# ETH_Wifi.net
KiCad netlist of a schematic drawn in Altium Designer
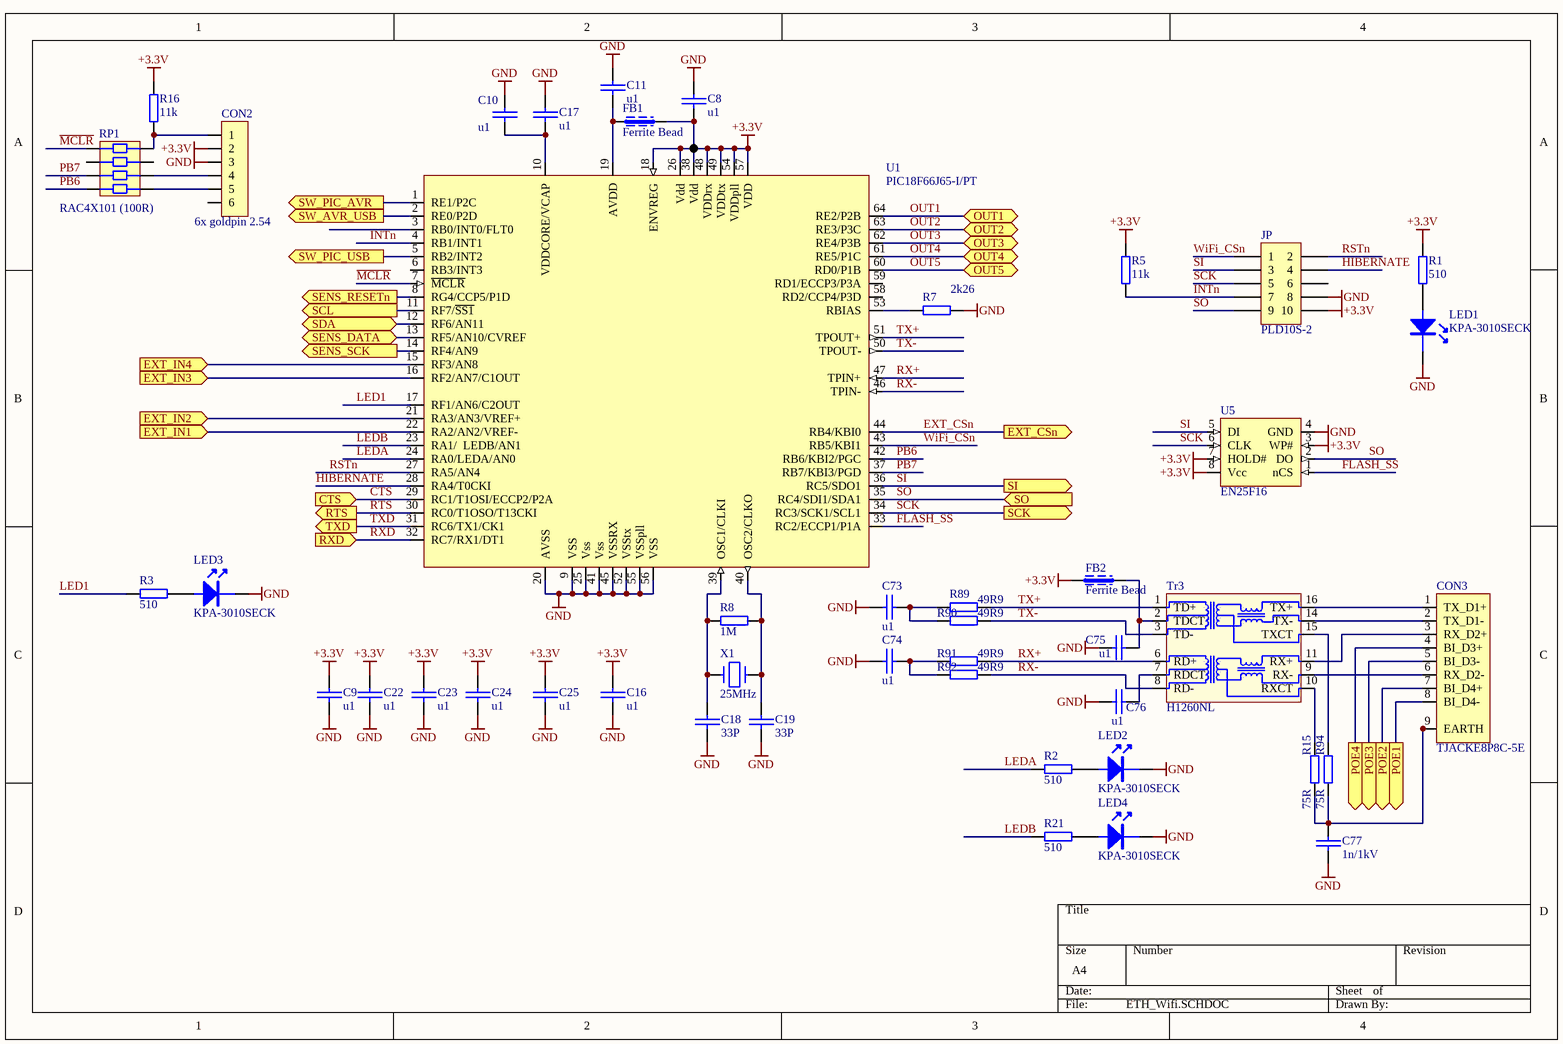
[diagram p0: ETH_Wifi.SCHDOC]

(export (version "E")
  (design (tool "Eeschema 10.0.6"))
  (components
    (comp (ref "C8")
      (value "u1")
      (footprint "0603")
      (description "Capacitor SMD")
      (libsource (lib "LIBRARY_SCH") (part "CAP_SMD"))
    )
    (comp (ref "C9")
      (value "u1")
      (footprint "0603")
      (description "Capacitor SMD")
      (libsource (lib "LIBRARY_SCH") (part "CAP_SMD"))
    )
    (comp (ref "C10")
      (value "u1")
      (footprint "0603")
      (description "Capacitor SMD")
      (libsource (lib "LIBRARY_SCH") (part "CAP_SMD"))
    )
    (comp (ref "C11")
      (value "u1")
      (footprint "0603")
      (description "Capacitor SMD")
      (libsource (lib "LIBRARY_SCH") (part "CAP_SMD"))
    )
    (comp (ref "C16")
      (value "u1")
      (footprint "0603")
      (description "Capacitor SMD")
      (libsource (lib "LIBRARY_SCH") (part "CAP_SMD"))
    )
    (comp (ref "C17")
      (value "u1")
      (footprint "0603")
      (description "Capacitor SMD")
      (libsource (lib "LIBRARY_SCH") (part "CAP_SMD"))
    )
    (comp (ref "C18")
      (value "33P")
      (footprint "0603")
      (description "Capacitor SMD")
      (libsource (lib "LIBRARY_SCH") (part "CAP_SMD"))
    )
    (comp (ref "C19")
      (value "33P")
      (footprint "0603")
      (description "Capacitor SMD")
      (libsource (lib "LIBRARY_SCH") (part "CAP_SMD"))
    )
    (comp (ref "C22")
      (value "u1")
      (footprint "0603")
      (description "Capacitor SMD")
      (libsource (lib "LIBRARY_SCH") (part "CAP_SMD"))
    )
    (comp (ref "C23")
      (value "u1")
      (footprint "0603")
      (description "Capacitor SMD")
      (libsource (lib "LIBRARY_SCH") (part "CAP_SMD"))
    )
    (comp (ref "C24")
      (value "u1")
      (footprint "0603")
      (description "Capacitor SMD")
      (libsource (lib "LIBRARY_SCH") (part "CAP_SMD"))
    )
    (comp (ref "C25")
      (value "u1")
      (footprint "0603")
      (description "Capacitor SMD")
      (libsource (lib "LIBRARY_SCH") (part "CAP_SMD"))
    )
    (comp (ref "C73")
      (value "u1")
      (footprint "0603")
      (description "Capacitor SMD")
      (libsource (lib "*") (part "CAP_SMD"))
    )
    (comp (ref "C74")
      (value "u1")
      (footprint "0603")
      (description "Capacitor SMD")
      (libsource (lib "*") (part "CAP_SMD"))
    )
    (comp (ref "C75")
      (value "u1")
      (footprint "0603")
      (description "Capacitor SMD")
      (libsource (lib "LIBRARY_SCH") (part "CAP_SMD"))
    )
    (comp (ref "C76")
      (value "u1")
      (footprint "0603")
      (description "Capacitor SMD")
      (libsource (lib "LIBRARY_SCH") (part "CAP_SMD"))
    )
    (comp (ref "C77")
      (value "1n/1kV")
      (footprint "cap_ceram")
      (description "Capacitor")
      (libsource (lib "LIBRARY_SCH") (part "CAP"))
    )
    (comp (ref "CON2") (value "6x goldpin 2.54") (footprint "SIP6") (libsource (lib "*") (part "CON6")))
    (comp (ref "CON3")
      (value "TJACKE8P8C-5E")
      (footprint "TJACKE8P8C-5E")
      (description "RJ 45 connector (Maritex)")
      (libsource (lib "LIBRARY_SCH") (part "CON_RJ45_shielded"))
    )
    (comp (ref "FB1")
      (value "Ferrite Bead")
      (footprint "0603")
      (description "ferrite bead")
      (libsource (lib "*") (part "L_FERRITE_BEAD"))
    )
    (comp (ref "FB2")
      (value "Ferrite Bead")
      (footprint "0603")
      (description "ferrite bead")
      (libsource (lib "*") (part "L_FERRITE_BEAD"))
    )
    (comp (ref "JP")
      (value "PLD10S-2")
      (footprint "HEADER5X2")
      (description "Goldpin 2.54mm")
      (libsource (lib "LIBRARY_SCH") (part "CON_HEADER 5X2"))
    )
    (comp (ref "LED1")
      (value "KPA-3010SECK")
      (footprint "LED_KPA3010")
      (description "LED (TME)")
      (libsource (lib "LIBRARY_SCH") (part "LED_SMD_90deg"))
    )
    (comp (ref "LED2")
      (value "KPA-3010SECK")
      (footprint "LED_KPA3010")
      (description "LED (TME)")
      (libsource (lib "LIBRARY_SCH") (part "LED_SMD_90deg"))
    )
    (comp (ref "LED3")
      (value "KPA-3010SECK")
      (footprint "LED_KPA3010")
      (description "LED (TME)")
      (libsource (lib "LIBRARY_SCH") (part "LED_SMD_90deg"))
    )
    (comp (ref "LED4")
      (value "KPA-3010SECK")
      (footprint "LED_KPA3010")
      (description "LED (TME)")
      (libsource (lib "LIBRARY_SCH") (part "LED_SMD_90deg"))
    )
    (comp (ref "R1")
      (value "510")
      (footprint "0603")
      (description "SMD Resistor")
      (libsource (lib "LIBRARY_SCH") (part "RES_SMD"))
    )
    (comp (ref "R2")
      (value "510")
      (footprint "0603")
      (description "SMD Resistor")
      (libsource (lib "LIBRARY_SCH") (part "RES_SMD"))
    )
    (comp (ref "R3")
      (value "510")
      (footprint "0603")
      (description "SMD Resistor")
      (libsource (lib "LIBRARY_SCH") (part "RES_SMD"))
    )
    (comp (ref "R5")
      (value "11k")
      (footprint "0603")
      (description "SMD Resistor")
      (libsource (lib "*") (part "RES_SMD"))
    )
    (comp (ref "R7")
      (value "2k26")
      (footprint "0603")
      (description "SMD Resistor")
      (libsource (lib "LIBRARY_SCH") (part "RES_SMD"))
    )
    (comp (ref "R8")
      (value "1M")
      (footprint "0603")
      (description "SMD Resistor")
      (libsource (lib "*") (part "RES_SMD"))
    )
    (comp (ref "R15")
      (value "75R")
      (footprint "0603")
      (description "SMD Resistor")
      (libsource (lib "*") (part "RES_SMD"))
    )
    (comp (ref "R16")
      (value "11k")
      (footprint "0603")
      (description "SMD Resistor")
      (libsource (lib "*") (part "RES_SMD"))
    )
    (comp (ref "R21")
      (value "510")
      (footprint "0603")
      (description "SMD Resistor")
      (libsource (lib "LIBRARY_SCH") (part "RES_SMD"))
    )
    (comp (ref "R89")
      (value "49R9")
      (footprint "0603")
      (description "SMD Resistor")
      (libsource (lib "LIBRARY_SCH") (part "RES_SMD"))
    )
    (comp (ref "R90")
      (value "49R9")
      (footprint "0603")
      (description "SMD Resistor")
      (libsource (lib "*") (part "RES_SMD"))
    )
    (comp (ref "R91")
      (value "49R9")
      (footprint "0603")
      (description "SMD Resistor")
      (libsource (lib "*") (part "RES_SMD"))
    )
    (comp (ref "R92")
      (value "49R9")
      (footprint "0603")
      (description "SMD Resistor")
      (libsource (lib "*") (part "RES_SMD"))
    )
    (comp (ref "R94")
      (value "75R")
      (footprint "0603")
      (description "SMD Resistor")
      (libsource (lib "*") (part "RES_SMD"))
    )
    (comp (ref "RP1")
      (value "RAC4X101 (100R)")
      (footprint "CAY-16")
      (description "Resistor network 1206 (4x0402) Maritex RAC4Xxxx")
      (libsource (lib "LIBRARY_SCH") (part "CAY-16"))
    )
    (comp (ref "Tr3")
      (value "H1260NL")
      (footprint "H1260NL")
      (description "ethernet trafo (TME)")
      (libsource (lib "*") (part "TR_H1260NL"))
    )
    (comp (ref "U1")
      (value "PIC18F66J65-I/PT")
      (footprint "TQFP64-MAX")
      (libsource (lib "LIBRARY_SCH") (part "PIC18F66J60"))
    )
    (comp (ref "U5")
      (value "EN25F16")
      (footprint "SO-8L")
      (description "FLASH (maritex)")
      (libsource (lib "LIBRARY_SCH") (part "MEM_EN25F16"))
    )
    (comp (ref "X1")
      (value "25MHz")
      (footprint "HC-49SM")
      (description "Crystal oscillator")
      (libsource (lib "LIBRARY_SCH") (part "CRYSTAL"))
    )
  )
  (nets
    (net (code "1") (name "+3.3V") (class "Default")
      (node (ref "C16") (pin "1") (pinfunction "1_1") (pintype "passive"))
      (node (ref "C22") (pin "1") (pinfunction "1_1") (pintype "passive"))
      (node (ref "C23") (pin "1") (pinfunction "1_1") (pintype "passive"))
      (node (ref "C24") (pin "1") (pinfunction "1_1") (pintype "passive"))
      (node (ref "C25") (pin "1") (pinfunction "1_1") (pintype "passive"))
      (node (ref "C8") (pin "2") (pinfunction "2_2") (pintype "passive"))
      (node (ref "C9") (pin "2") (pinfunction "2_2") (pintype "passive"))
      (node (ref "CON2") (pin "2") (pinfunction "2_2") (pintype "passive"))
      (node (ref "FB1") (pin "2") (pinfunction "2_2") (pintype "passive"))
      (node (ref "FB2") (pin "1") (pinfunction "1_1") (pintype "passive"))
      (node (ref "JP") (pin "10") (pinfunction "10_10") (pintype "passive"))
      (node (ref "R1") (pin "1") (pinfunction "1_1") (pintype "passive"))
      (node (ref "R16") (pin "2") (pinfunction "2_2") (pintype "passive"))
      (node (ref "R5") (pin "2") (pinfunction "2_2") (pintype "passive"))
      (node (ref "U1") (pin "18") (pinfunction "ENVREG_18") (pintype "input"))
      (node (ref "U1") (pin "26") (pinfunction "Vdd_26") (pintype "power_in"))
      (node (ref "U1") (pin "38") (pinfunction "Vdd_38") (pintype "power_in"))
      (node (ref "U1") (pin "48") (pinfunction "VDDrx_48") (pintype "power_in"))
      (node (ref "U1") (pin "49") (pinfunction "VDDtx_49") (pintype "power_in"))
      (node (ref "U1") (pin "54") (pinfunction "VDDpll_54") (pintype "power_in"))
      (node (ref "U1") (pin "57") (pinfunction "VDD_57") (pintype "power_in"))
      (node (ref "U5") (pin "3") (pinfunction "WP#_3") (pintype "input"))
      (node (ref "U5") (pin "7") (pinfunction "HOLD#_7") (pintype "input"))
      (node (ref "U5") (pin "8") (pinfunction "Vcc_8") (pintype "passive"))
    )
    (net (code "2") (name "/CTS") (class "Default")
      (node (ref "U1") (pin "29") (pinfunction "RC1/T1OSI/ECCP2/P2A_29") (pintype "bidirectional"))
    )
    (net (code "3") (name "/EXT_CSn") (class "Default")
      (node (ref "U1") (pin "44") (pinfunction "RB4/KBI0_44") (pintype "bidirectional"))
    )
    (net (code "4") (name "/EXT_IN1") (class "Default")
      (node (ref "U1") (pin "22") (pinfunction "RA2/AN2/VREF-_22") (pintype "bidirectional"))
    )
    (net (code "5") (name "/EXT_IN2") (class "Default")
      (node (ref "U1") (pin "21") (pinfunction "RA3/AN3/VREF+_21") (pintype "bidirectional"))
    )
    (net (code "6") (name "/EXT_IN3") (class "Default")
      (node (ref "U1") (pin "16") (pinfunction "RF2/AN7/C1OUT_16") (pintype "bidirectional"))
    )
    (net (code "7") (name "/EXT_IN4") (class "Default")
      (node (ref "U1") (pin "15") (pinfunction "RF3/AN8_15") (pintype "bidirectional"))
    )
    (net (code "8") (name "/FLASH_SS") (class "Default")
      (node (ref "U1") (pin "33") (pinfunction "RC2/ECCP1/P1A_33") (pintype "bidirectional"))
      (node (ref "U5") (pin "1") (pinfunction "nCS_1") (pintype "input"))
    )
    (net (code "9") (name "/HIBERNATE") (class "Default")
      (node (ref "JP") (pin "4") (pinfunction "4_4") (pintype "passive"))
      (node (ref "U1") (pin "28") (pinfunction "RA4/T0CKI_28") (pintype "bidirectional"))
    )
    (net (code "10") (name "/INTn") (class "Default")
      (node (ref "JP") (pin "7") (pinfunction "7_7") (pintype "passive"))
      (node (ref "R5") (pin "1") (pinfunction "1_1") (pintype "passive"))
      (node (ref "U1") (pin "4") (pinfunction "RB1/INT1_4") (pintype "bidirectional"))
    )
    (net (code "11") (name "/LED1") (class "Default")
      (node (ref "R3") (pin "2") (pinfunction "2_2") (pintype "passive"))
      (node (ref "U1") (pin "17") (pinfunction "RF1/AN6/C2OUT_17") (pintype "bidirectional"))
    )
    (net (code "12") (name "/LEDA") (class "Default")
      (node (ref "R2") (pin "2") (pinfunction "2_2") (pintype "passive"))
      (node (ref "U1") (pin "24") (pinfunction "RA0/LEDA/AN0_24") (pintype "bidirectional"))
    )
    (net (code "13") (name "/LEDB") (class "Default")
      (node (ref "R21") (pin "2") (pinfunction "2_2") (pintype "passive"))
      (node (ref "U1") (pin "23") (pinfunction "RA1/__LEDB/AN1_23") (pintype "bidirectional"))
    )
    (net (code "14") (name "/OUT1") (class "Default")
      (node (ref "U1") (pin "64") (pinfunction "RE2/P2B_64") (pintype "bidirectional"))
    )
    (net (code "15") (name "/OUT2") (class "Default")
      (node (ref "U1") (pin "63") (pinfunction "RE3/P3C_63") (pintype "bidirectional"))
    )
    (net (code "16") (name "/OUT3") (class "Default")
      (node (ref "U1") (pin "62") (pinfunction "RE4/P3B_62") (pintype "bidirectional"))
    )
    (net (code "17") (name "/OUT4") (class "Default")
      (node (ref "U1") (pin "61") (pinfunction "RE5/P1C_61") (pintype "bidirectional"))
    )
    (net (code "18") (name "/OUT5") (class "Default")
      (node (ref "U1") (pin "60") (pinfunction "RD0/P1B_60") (pintype "bidirectional"))
    )
    (net (code "19") (name "/PB6") (class "Default")
      (node (ref "RP1") (pin "4") (pinfunction "4_4") (pintype "passive"))
      (node (ref "U1") (pin "42") (pinfunction "RB6/KBI2/PGC_42") (pintype "bidirectional"))
    )
    (net (code "20") (name "/PB7") (class "Default")
      (node (ref "RP1") (pin "3") (pinfunction "3_3") (pintype "passive"))
      (node (ref "U1") (pin "37") (pinfunction "RB7/KBI3/PGD_37") (pintype "bidirectional"))
    )
    (net (code "21") (name "/POE1") (class "Default")
      (node (ref "CON3") (pin "8") (pinfunction "BI_D4-_8") (pintype "passive"))
    )
    (net (code "22") (name "/POE2") (class "Default")
      (node (ref "CON3") (pin "7") (pinfunction "BI_D4+_7") (pintype "passive"))
    )
    (net (code "23") (name "/POE3") (class "Default")
      (node (ref "CON3") (pin "5") (pinfunction "BI_D3-_5") (pintype "passive"))
    )
    (net (code "24") (name "/POE4") (class "Default")
      (node (ref "CON3") (pin "4") (pinfunction "BI_D3+_4") (pintype "passive"))
    )
    (net (code "25") (name "/RSTn") (class "Default")
      (node (ref "JP") (pin "2") (pinfunction "2_2") (pintype "passive"))
      (node (ref "U1") (pin "27") (pinfunction "RA5/AN4_27") (pintype "bidirectional"))
    )
    (net (code "26") (name "/RTS") (class "Default")
      (node (ref "U1") (pin "30") (pinfunction "RC0/T1OSO/T13CKI_30") (pintype "bidirectional"))
    )
    (net (code "27") (name "/RX+") (class "Default")
      (node (ref "R91") (pin "2") (pinfunction "2_2") (pintype "passive"))
      (node (ref "Tr3") (pin "6") (pinfunction "RD+_6") (pintype "passive"))
      (node (ref "U1") (pin "47") (pinfunction "TPIN+_47") (pintype "input"))
    )
    (net (code "28") (name "/RX-") (class "Default")
      (node (ref "R92") (pin "2") (pinfunction "2_2") (pintype "passive"))
      (node (ref "Tr3") (pin "8") (pinfunction "RD-_8") (pintype "passive"))
      (node (ref "U1") (pin "46") (pinfunction "TPIN-_46") (pintype "input"))
    )
    (net (code "29") (name "/RXD") (class "Default")
      (node (ref "U1") (pin "32") (pinfunction "RC7/RX1/DT1_32") (pintype "bidirectional"))
    )
    (net (code "30") (name "/SCK") (class "Default")
      (node (ref "JP") (pin "5") (pinfunction "5_5") (pintype "passive"))
      (node (ref "U1") (pin "34") (pinfunction "RC3/SCK1/SCL1_34") (pintype "bidirectional"))
      (node (ref "U5") (pin "6") (pinfunction "CLK_6") (pintype "input"))
    )
    (net (code "31") (name "/SCL") (class "Default")
      (node (ref "U1") (pin "11") (pinfunction "RF7/~{SS1}_11") (pintype "bidirectional"))
    )
    (net (code "32") (name "/SDA") (class "Default")
      (node (ref "U1") (pin "12") (pinfunction "RF6/AN11_12") (pintype "bidirectional"))
    )
    (net (code "33") (name "/SENS_DATA") (class "Default")
      (node (ref "U1") (pin "13") (pinfunction "RF5/AN10/CVREF_13") (pintype "bidirectional"))
    )
    (net (code "34") (name "/SENS_RESETn") (class "Default")
      (node (ref "U1") (pin "8") (pinfunction "RG4/CCP5/P1D_8") (pintype "bidirectional"))
    )
    (net (code "35") (name "/SENS_SCK") (class "Default")
      (node (ref "U1") (pin "14") (pinfunction "RF4/AN9_14") (pintype "bidirectional"))
    )
    (net (code "36") (name "/SI") (class "Default")
      (node (ref "JP") (pin "3") (pinfunction "3_3") (pintype "passive"))
      (node (ref "U1") (pin "36") (pinfunction "RC5/SDO1_36") (pintype "bidirectional"))
      (node (ref "U5") (pin "5") (pinfunction "DI_5") (pintype "input"))
    )
    (net (code "37") (name "/SO") (class "Default")
      (node (ref "JP") (pin "9") (pinfunction "9_9") (pintype "passive"))
      (node (ref "U1") (pin "35") (pinfunction "RC4/SDI1/SDA1_35") (pintype "bidirectional"))
      (node (ref "U5") (pin "2") (pinfunction "DO_2") (pintype "output"))
    )
    (net (code "38") (name "/SW_AVR_USB") (class "Default")
      (node (ref "U1") (pin "2") (pinfunction "RE0/P2D_2") (pintype "bidirectional"))
    )
    (net (code "39") (name "/SW_PIC_AVR") (class "Default")
      (node (ref "U1") (pin "1") (pinfunction "RE1/P2C_1") (pintype "bidirectional"))
    )
    (net (code "40") (name "/SW_PIC_USB") (class "Default")
      (node (ref "U1") (pin "5") (pinfunction "RB2/INT2_5") (pintype "bidirectional"))
    )
    (net (code "41") (name "/TX+") (class "Default")
      (node (ref "R89") (pin "2") (pinfunction "2_2") (pintype "passive"))
      (node (ref "Tr3") (pin "1") (pinfunction "TD+_1") (pintype "passive"))
      (node (ref "U1") (pin "51") (pinfunction "TPOUT+_51") (pintype "output"))
    )
    (net (code "42") (name "/TX-") (class "Default")
      (node (ref "R90") (pin "2") (pinfunction "2_2") (pintype "passive"))
      (node (ref "Tr3") (pin "3") (pinfunction "TD-_3") (pintype "passive"))
      (node (ref "U1") (pin "50") (pinfunction "TPOUT-_50") (pintype "output"))
    )
    (net (code "43") (name "/TXD") (class "Default")
      (node (ref "U1") (pin "31") (pinfunction "RC6/TX1/CK1_31") (pintype "bidirectional"))
    )
    (net (code "44") (name "/WiFi_CSn") (class "Default")
      (node (ref "JP") (pin "1") (pinfunction "1_1") (pintype "passive"))
      (node (ref "U1") (pin "43") (pinfunction "RB5/KBI1_43") (pintype "bidirectional"))
    )
    (net (code "45") (name "/~{MCLR}") (class "Default")
      (node (ref "RP1") (pin "1") (pinfunction "1_1") (pintype "passive"))
      (node (ref "U1") (pin "7") (pinfunction "~{MCLR}_7") (pintype "input"))
    )
    (net (code "46") (name "GND") (class "Default")
      (node (ref "C10") (pin "1") (pinfunction "1_1") (pintype "passive"))
      (node (ref "C11") (pin "1") (pinfunction "1_1") (pintype "passive"))
      (node (ref "C16") (pin "2") (pinfunction "2_2") (pintype "passive"))
      (node (ref "C17") (pin "1") (pinfunction "1_1") (pintype "passive"))
      (node (ref "C18") (pin "1") (pinfunction "1_1") (pintype "passive"))
      (node (ref "C19") (pin "1") (pinfunction "1_1") (pintype "passive"))
      (node (ref "C22") (pin "2") (pinfunction "2_2") (pintype "passive"))
      (node (ref "C23") (pin "2") (pinfunction "2_2") (pintype "passive"))
      (node (ref "C24") (pin "2") (pinfunction "2_2") (pintype "passive"))
      (node (ref "C25") (pin "2") (pinfunction "2_2") (pintype "passive"))
      (node (ref "C73") (pin "1") (pinfunction "1_1") (pintype "passive"))
      (node (ref "C74") (pin "1") (pinfunction "1_1") (pintype "passive"))
      (node (ref "C75") (pin "1") (pinfunction "1_1") (pintype "passive"))
      (node (ref "C76") (pin "1") (pinfunction "1_1") (pintype "passive"))
      (node (ref "C77") (pin "2") (pinfunction "2_2") (pintype "passive"))
      (node (ref "C8") (pin "1") (pinfunction "1_1") (pintype "passive"))
      (node (ref "C9") (pin "1") (pinfunction "1_1") (pintype "passive"))
      (node (ref "CON2") (pin "3") (pinfunction "3_3") (pintype "passive"))
      (node (ref "JP") (pin "8") (pinfunction "8_8") (pintype "passive"))
      (node (ref "LED1") (pin "K") (pinfunction "K_K") (pintype "passive"))
      (node (ref "LED2") (pin "K") (pinfunction "K_K") (pintype "passive"))
      (node (ref "LED3") (pin "K") (pinfunction "K_K") (pintype "passive"))
      (node (ref "LED4") (pin "K") (pinfunction "K_K") (pintype "passive"))
      (node (ref "R7") (pin "2") (pinfunction "2_2") (pintype "passive"))
      (node (ref "U1") (pin "20") (pinfunction "AVSS_20") (pintype "power_in"))
      (node (ref "U1") (pin "25") (pinfunction "Vss_25") (pintype "power_in"))
      (node (ref "U1") (pin "41") (pinfunction "Vss_41") (pintype "power_in"))
      (node (ref "U1") (pin "45") (pinfunction "VSSRX_45") (pintype "power_in"))
      (node (ref "U1") (pin "52") (pinfunction "VSStx_52") (pintype "power_in"))
      (node (ref "U1") (pin "55") (pinfunction "VSSpll_55") (pintype "power_in"))
      (node (ref "U1") (pin "56") (pinfunction "VSS_56") (pintype "power_in"))
      (node (ref "U1") (pin "9") (pinfunction "VSS_9") (pintype "power_in"))
      (node (ref "U5") (pin "4") (pinfunction "GND_4") (pintype "passive"))
    )
    (net (code "47") (name "Net-(C73-Pad2)") (class "Default")
      (node (ref "C73") (pin "2") (pinfunction "2_2") (pintype "passive"))
      (node (ref "R89") (pin "1") (pinfunction "1_1") (pintype "passive"))
      (node (ref "R90") (pin "1") (pinfunction "1_1") (pintype "passive"))
    )
    (net (code "48") (name "Net-(C74-Pad2)") (class "Default")
      (node (ref "C74") (pin "2") (pinfunction "2_2") (pintype "passive"))
      (node (ref "R91") (pin "1") (pinfunction "1_1") (pintype "passive"))
      (node (ref "R92") (pin "1") (pinfunction "1_1") (pintype "passive"))
    )
    (net (code "49") (name "Net-(CON2-Pad1)") (class "Default")
      (node (ref "CON2") (pin "1") (pinfunction "1_1") (pintype "passive"))
      (node (ref "R16") (pin "1") (pinfunction "1_1") (pintype "passive"))
      (node (ref "RP1") (pin "8") (pinfunction "8_8") (pintype "passive"))
    )
    (net (code "50") (name "Net-(CON2-Pad4)") (class "Default")
      (node (ref "CON2") (pin "4") (pinfunction "4_4") (pintype "passive"))
      (node (ref "RP1") (pin "6") (pinfunction "6_6") (pintype "passive"))
    )
    (net (code "51") (name "Net-(CON2-Pad5)") (class "Default")
      (node (ref "CON2") (pin "5") (pinfunction "5_5") (pintype "passive"))
      (node (ref "RP1") (pin "5") (pinfunction "5_5") (pintype "passive"))
    )
    (net (code "52") (name "Net-(CON3-EARTH)") (class "Default")
      (node (ref "C77") (pin "1") (pinfunction "1_1") (pintype "passive"))
      (node (ref "CON3") (pin "9") (pinfunction "EARTH_9") (pintype "passive"))
      (node (ref "CON3") (pin "9b") (pinfunction "9_9b") (pintype "passive"))
      (node (ref "CON3") (pin "9c") (pinfunction "9_9c") (pintype "passive"))
      (node (ref "CON3") (pin "9d") (pinfunction "9_9d") (pintype "passive"))
      (node (ref "R15") (pin "1") (pinfunction "1_1") (pintype "passive"))
      (node (ref "R94") (pin "1") (pinfunction "1_1") (pintype "passive"))
    )
    (net (code "53") (name "Net-(CON3-RX_D2+)") (class "Default")
      (node (ref "CON3") (pin "3") (pinfunction "RX_D2+_3") (pintype "passive"))
      (node (ref "Tr3") (pin "11") (pinfunction "RX+_11") (pintype "power_in"))
    )
    (net (code "54") (name "Net-(CON3-RX_D2-)") (class "Default")
      (node (ref "CON3") (pin "6") (pinfunction "RX_D2-_6") (pintype "passive"))
      (node (ref "Tr3") (pin "9") (pinfunction "RX-_9") (pintype "power_in"))
    )
    (net (code "55") (name "Net-(CON3-TX_D1+)") (class "Default")
      (node (ref "CON3") (pin "1") (pinfunction "TX_D1+_1") (pintype "passive"))
      (node (ref "Tr3") (pin "16") (pinfunction "TX+_16") (pintype "power_in"))
    )
    (net (code "56") (name "Net-(CON3-TX_D1-)") (class "Default")
      (node (ref "CON3") (pin "2") (pinfunction "TX_D1-_2") (pintype "passive"))
      (node (ref "Tr3") (pin "14") (pinfunction "TX-_14") (pintype "power_in"))
    )
    (net (code "57") (name "Net-(LED1-PadA)") (class "Default")
      (node (ref "LED1") (pin "A") (pinfunction "A_A") (pintype "passive"))
      (node (ref "R1") (pin "2") (pinfunction "2_2") (pintype "passive"))
    )
    (net (code "58") (name "Net-(LED2-PadA)") (class "Default")
      (node (ref "LED2") (pin "A") (pinfunction "A_A") (pintype "passive"))
      (node (ref "R2") (pin "1") (pinfunction "1_1") (pintype "passive"))
    )
    (net (code "59") (name "Net-(LED3-PadA)") (class "Default")
      (node (ref "LED3") (pin "A") (pinfunction "A_A") (pintype "passive"))
      (node (ref "R3") (pin "1") (pinfunction "1_1") (pintype "passive"))
    )
    (net (code "60") (name "Net-(LED4-PadA)") (class "Default")
      (node (ref "LED4") (pin "A") (pinfunction "A_A") (pintype "passive"))
      (node (ref "R21") (pin "1") (pinfunction "1_1") (pintype "passive"))
    )
    (net (code "61") (name "Net-(Tr3-RDCT)") (class "Default")
      (node (ref "C76") (pin "2") (pinfunction "2_2") (pintype "passive"))
      (node (ref "Tr3") (pin "7") (pinfunction "RDCT_7") (pintype "passive"))
    )
    (net (code "62") (name "Net-(Tr3-RXCT)") (class "Default")
      (node (ref "R15") (pin "2") (pinfunction "2_2") (pintype "passive"))
      (node (ref "Tr3") (pin "10") (pinfunction "RXCT_10") (pintype "power_in"))
    )
    (net (code "63") (name "Net-(Tr3-TDCT)") (class "Default")
      (node (ref "C75") (pin "2") (pinfunction "2_2") (pintype "passive"))
      (node (ref "FB2") (pin "2") (pinfunction "2_2") (pintype "passive"))
      (node (ref "Tr3") (pin "2") (pinfunction "TDCT_2") (pintype "passive"))
    )
    (net (code "64") (name "Net-(Tr3-TXCT)") (class "Default")
      (node (ref "R94") (pin "2") (pinfunction "2_2") (pintype "passive"))
      (node (ref "Tr3") (pin "15") (pinfunction "TXCT_15") (pintype "power_in"))
    )
    (net (code "65") (name "Net-(U1-AVDD)") (class "Default")
      (node (ref "C11") (pin "2") (pinfunction "2_2") (pintype "passive"))
      (node (ref "FB1") (pin "1") (pinfunction "1_1") (pintype "passive"))
      (node (ref "U1") (pin "19") (pinfunction "AVDD_19") (pintype "power_in"))
    )
    (net (code "66") (name "Net-(U1-OSC1{slash}CLKI)") (class "Default")
      (node (ref "C18") (pin "2") (pinfunction "2_2") (pintype "passive"))
      (node (ref "R8") (pin "1") (pinfunction "1_1") (pintype "passive"))
      (node (ref "U1") (pin "39") (pinfunction "OSC1/CLKI_39") (pintype "input"))
      (node (ref "X1") (pin "1") (pinfunction "1_1") (pintype "passive"))
    )
    (net (code "67") (name "Net-(U1-OSC2{slash}CLKO)") (class "Default")
      (node (ref "C19") (pin "2") (pinfunction "2_2") (pintype "passive"))
      (node (ref "R8") (pin "2") (pinfunction "2_2") (pintype "passive"))
      (node (ref "U1") (pin "40") (pinfunction "OSC2/CLKO_40") (pintype "output"))
      (node (ref "X1") (pin "2") (pinfunction "2_2") (pintype "passive"))
    )
    (net (code "68") (name "Net-(U1-RBIAS)") (class "Default")
      (node (ref "R7") (pin "1") (pinfunction "1_1") (pintype "passive"))
      (node (ref "U1") (pin "53") (pinfunction "RBIAS_53") (pintype "passive"))
    )
    (net (code "69") (name "Net-(U1-VDDCORE{slash}VCAP)") (class "Default")
      (node (ref "C10") (pin "2") (pinfunction "2_2") (pintype "passive"))
      (node (ref "C17") (pin "2") (pinfunction "2_2") (pintype "passive"))
      (node (ref "U1") (pin "10") (pinfunction "VDDCORE/VCAP_10") (pintype "power_in"))
    )
    (net (code "70") (name "unconnected-(CON2-Pad6)") (class "Default")
      (node (ref "CON2") (pin "6") (pinfunction "6_6") (pintype "passive"))
    )
    (net (code "71") (name "unconnected-(JP-Pad6)") (class "Default")
      (node (ref "JP") (pin "6") (pinfunction "6_6") (pintype "passive"))
    )
    (net (code "72") (name "unconnected-(RP1-Pad2)") (class "Default")
      (node (ref "RP1") (pin "2") (pinfunction "2_2") (pintype "passive"))
    )
    (net (code "73") (name "unconnected-(RP1-Pad7)") (class "Default")
      (node (ref "RP1") (pin "7") (pinfunction "7_7") (pintype "passive"))
    )
    (net (code "74") (name "unconnected-(U1-RB0{slash}INT0{slash}FLT0-Pad3)") (class "Default")
      (node (ref "U1") (pin "3") (pinfunction "RB0/INT0/FLT0_3") (pintype "bidirectional"))
    )
    (net (code "75") (name "unconnected-(U1-RB3{slash}INT3-Pad6)") (class "Default")
      (node (ref "U1") (pin "6") (pinfunction "RB3/INT3_6") (pintype "bidirectional"))
    )
    (net (code "76") (name "unconnected-(U1-RD1{slash}ECCP3{slash}P3A-Pad59)") (class "Default")
      (node (ref "U1") (pin "59") (pinfunction "RD1/ECCP3/P3A_59") (pintype "bidirectional"))
    )
    (net (code "77") (name "unconnected-(U1-RD2{slash}CCP4{slash}P3D-Pad58)") (class "Default")
      (node (ref "U1") (pin "58") (pinfunction "RD2/CCP4/P3D_58") (pintype "bidirectional"))
    )
  )
)
